# 07_-_SD.net
KiCad netlist of a schematic drawn in Altium Designer
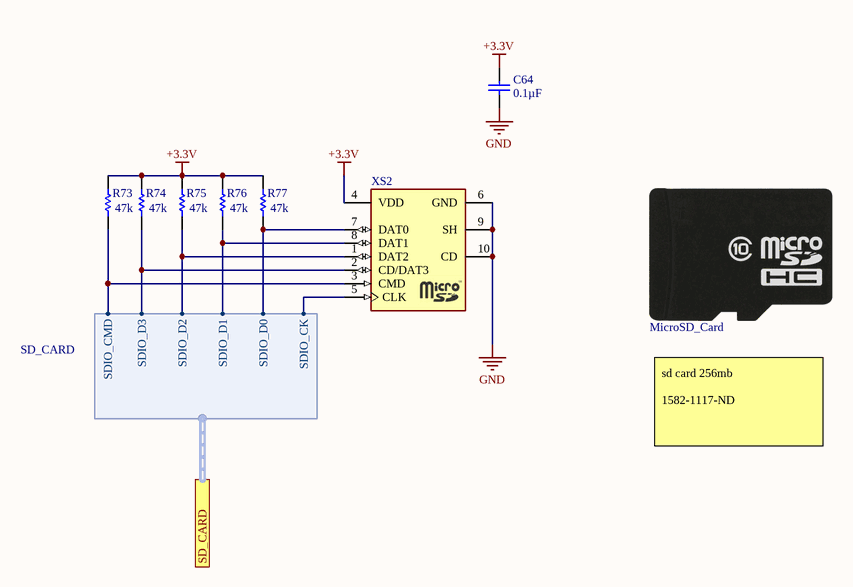
[diagram p0: [07] - SD.SchDoc]

(export (version "E")
  (design (tool "Eeschema 10.0.6"))
  (components
    (comp (ref "*1")
      (value "MicroSD_Card")
      (fields
        (field (name "MANUFACTURER") "Apacer")
        (field (name "MANUFACTURER PART NUMBER") "AP-MSD256ISI-1T")
      )
      (libsource (lib "Light_Control_BM-v.1.0-2018") (part "MicroSD_Card"))
    )
    (comp (ref "C64")
      (value "Capacitor")
      (footprint "Blue Tractor-2021:0603_C")
      (description "Chip Capacitor Nonpolar")
      (fields
        (field (name "MANUFACTURER") "Kemet")
        (field (name "MANUFACTURER PART NUMBER") "C0603C104K5RACTU")
        (field (name "CAPACITANCE") "0.1µF")
      )
      (libsource (lib "Altium_Library") (part "Capacitor"))
    )
    (comp (ref "R73")
      (value "Res1")
      (footprint "Blue Tractor-2021:0603_R")
      (description "Chip Resistor")
      (fields
        (field (name "MANUFACTURER") "Panasonic")
        (field (name "MANUFACTURER PART NUMBER") "ERJ-3EKF4702V")
        (field (name "RESISTANCE") "47k")
      )
      (libsource (lib "Altium_Library") (part "Res1"))
    )
    (comp (ref "R74")
      (value "Res1")
      (footprint "Blue Tractor-2021:0603_R")
      (description "Chip Resistor")
      (fields
        (field (name "MANUFACTURER") "Panasonic")
        (field (name "MANUFACTURER PART NUMBER") "ERJ-3EKF4702V")
        (field (name "RESISTANCE") "47k")
      )
      (libsource (lib "Altium_Library") (part "Res1"))
    )
    (comp (ref "R75")
      (value "Res1")
      (footprint "Blue Tractor-2021:0603_R")
      (description "Chip Resistor")
      (fields
        (field (name "MANUFACTURER") "Panasonic")
        (field (name "MANUFACTURER PART NUMBER") "ERJ-3EKF4702V")
        (field (name "RESISTANCE") "47k")
      )
      (libsource (lib "Altium_Library") (part "Res1"))
    )
    (comp (ref "R76")
      (value "Res1")
      (footprint "Blue Tractor-2021:0603_R")
      (description "Chip Resistor")
      (fields
        (field (name "MANUFACTURER") "Panasonic")
        (field (name "MANUFACTURER PART NUMBER") "ERJ-3EKF4702V")
        (field (name "RESISTANCE") "47k")
      )
      (libsource (lib "Altium_Library") (part "Res1"))
    )
    (comp (ref "R77")
      (value "Res1")
      (footprint "Blue Tractor-2021:0603_R")
      (description "Chip Resistor")
      (fields
        (field (name "MANUFACTURER") "Panasonic")
        (field (name "MANUFACTURER PART NUMBER") "ERJ-3EKF4702V")
        (field (name "RESISTANCE") "47k")
      )
      (libsource (lib "Altium_Library") (part "Res1"))
    )
    (comp (ref "XS2")
      (value "~")
      (footprint "MICROSD")
      (description "=Description")
      (fields (field (name "MANUFACTURER") "Molex") (field (name "MANUFACTURER PART NUMBER") "105162-0001"))
      (libsource (lib "CVC_Meter") (part "MICROSD"))
    )
  )
  (nets
    (net (code "2") (name "+3.3V") (class "Default")
      (node (ref "C64") (pin "2") (pinfunction "2_2") (pintype "passive"))
      (node (ref "R73") (pin "2") (pinfunction "2_2") (pintype "passive"))
      (node (ref "R74") (pin "2") (pinfunction "2_2") (pintype "passive"))
      (node (ref "R75") (pin "2") (pinfunction "2_2") (pintype "passive"))
      (node (ref "R76") (pin "2") (pinfunction "2_2") (pintype "passive"))
      (node (ref "R77") (pin "2") (pinfunction "2_2") (pintype "passive"))
      (node (ref "XS2") (pin "4") (pinfunction "VDD_4") (pintype "power_in"))
    )
    (net (code "3") (name "/SDIO_CK") (class "Default")
      (node (ref "XS2") (pin "5") (pinfunction "CLK_5") (pintype "input"))
    )
    (net (code "4") (name "/SDIO_CMD") (class "Default")
      (node (ref "R73") (pin "1") (pinfunction "1_1") (pintype "passive"))
      (node (ref "XS2") (pin "3") (pinfunction "CMD_3") (pintype "input"))
    )
    (net (code "5") (name "/SDIO_D0") (class "Default")
      (node (ref "R77") (pin "1") (pinfunction "1_1") (pintype "passive"))
      (node (ref "XS2") (pin "7") (pinfunction "DAT0_7") (pintype "bidirectional"))
    )
    (net (code "6") (name "/SDIO_D1") (class "Default")
      (node (ref "R76") (pin "1") (pinfunction "1_1") (pintype "passive"))
      (node (ref "XS2") (pin "8") (pinfunction "DAT1_8") (pintype "bidirectional"))
    )
    (net (code "7") (name "/SDIO_D2") (class "Default")
      (node (ref "R75") (pin "1") (pinfunction "1_1") (pintype "passive"))
      (node (ref "XS2") (pin "1") (pinfunction "DAT2_1") (pintype "bidirectional"))
    )
    (net (code "8") (name "/SDIO_D3") (class "Default")
      (node (ref "R74") (pin "1") (pinfunction "1_1") (pintype "passive"))
      (node (ref "XS2") (pin "2") (pinfunction "CD/DAT3_2") (pintype "bidirectional"))
    )
    (net (code "10") (name "GND") (class "Default")
      (node (ref "C64") (pin "1") (pinfunction "1_1") (pintype "passive"))
      (node (ref "XS2") (pin "10") (pinfunction "CD_10") (pintype "passive"))
      (node (ref "XS2") (pin "6") (pinfunction "GND_6") (pintype "power_in"))
      (node (ref "XS2") (pin "9") (pinfunction "SH_9") (pintype "passive"))
    )
  )
)
